# IST8310.net
KiCad netlist of a schematic drawn in Altium Designer
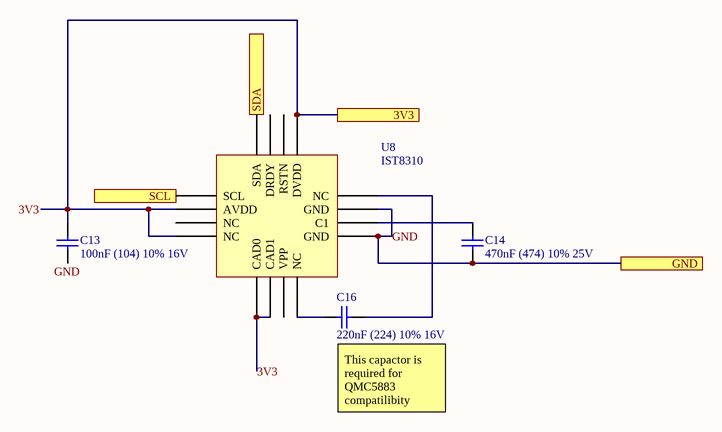
[diagram p0: IST8310.SchDoc]

(export (version "E")
  (design (tool "Eeschema 10.0.6"))
  (components
    (comp (ref "C13")
      (value "100nF (104) 10% 16V")
      (footprint "0402_C")
      (description "贴片电容")
      (libsource (lib "Miscellaneous Devices LC") (part "0402 100nF (104) 10% 16V"))
    )
    (comp (ref "C14")
      (value "470nF (474) 10% 25V")
      (footprint "0603_C")
      (description "贴片电容")
      (libsource (lib "Miscellaneous Devices LC") (part "0603 470nF (474) 10% 25V"))
    )
    (comp (ref "C16")
      (value "220nF (224) 10% 16V")
      (footprint "0402_C")
      (description "贴片电容")
      (libsource (lib "Miscellaneous Devices LC") (part "0402 220nF (224) 10% 16V"))
    )
    (comp (ref "U8")
      (value "IST8310")
      (footprint "IST8310_LGA16")
      (libsource (lib "IST8310") (part "IST8310"))
    )
  )
  (nets
    (net (code "1") (name "/3V3") (class "Default")
      (node (ref "C13") (pin "1") (pinfunction "1_1") (pintype "passive"))
      (node (ref "U8") (pin "13") (pinfunction "DVDD_13") (pintype "passive"))
      (node (ref "U8") (pin "2") (pinfunction "AVDD_2") (pintype "passive"))
      (node (ref "U8") (pin "4") (pinfunction "NC_4") (pintype "passive"))
      (node (ref "U8") (pin "5") (pinfunction "CAD0_5") (pintype "passive"))
      (node (ref "U8") (pin "6") (pinfunction "CAD1_6") (pintype "passive"))
    )
    (net (code "2") (name "/GND") (class "Default")
      (node (ref "C13") (pin "2") (pinfunction "2_2") (pintype "passive"))
      (node (ref "C14") (pin "1") (pinfunction "1_1") (pintype "passive"))
      (node (ref "U8") (pin "11") (pinfunction "GND_11") (pintype "passive"))
      (node (ref "U8") (pin "9") (pinfunction "GND_9") (pintype "passive"))
    )
    (net (code "3") (name "/SCL") (class "Default")
      (node (ref "U8") (pin "1") (pinfunction "SCL_1") (pintype "passive"))
    )
    (net (code "4") (name "/SDA") (class "Default")
      (node (ref "U8") (pin "16") (pinfunction "SDA_16") (pintype "passive"))
    )
    (net (code "5") (name "Net-(C16-Pad1)") (class "Default")
      (node (ref "C16") (pin "1") (pinfunction "1_1") (pintype "passive"))
      (node (ref "U8") (pin "12") (pinfunction "NC_12") (pintype "passive"))
    )
    (net (code "6") (name "Net-(C16-Pad2)") (class "Default")
      (node (ref "C16") (pin "2") (pinfunction "2_2") (pintype "passive"))
      (node (ref "U8") (pin "8") (pinfunction "NC_8") (pintype "passive"))
    )
    (net (code "7") (name "Net-(U8-C1)") (class "Default")
      (node (ref "C14") (pin "2") (pinfunction "2_2") (pintype "passive"))
      (node (ref "U8") (pin "10") (pinfunction "C1_10") (pintype "passive"))
    )
    (net (code "8") (name "unconnected-(U8-DRDY-Pad15)") (class "Default")
      (node (ref "U8") (pin "15") (pinfunction "DRDY_15") (pintype "passive"))
    )
    (net (code "9") (name "unconnected-(U8-NC-Pad3)") (class "Default")
      (node (ref "U8") (pin "3") (pinfunction "NC_3") (pintype "passive"))
    )
    (net (code "10") (name "unconnected-(U8-RSTN-Pad14)") (class "Default")
      (node (ref "U8") (pin "14") (pinfunction "RSTN_14") (pintype "passive"))
    )
    (net (code "11") (name "unconnected-(U8-VPP-Pad7)") (class "Default")
      (node (ref "U8") (pin "7") (pinfunction "VPP_7") (pintype "passive"))
    )
  )
)
